# SCH_My-1st-flashing-led-pcb_2025-11-08.net
KiCad netlist of a schematic drawn in EasyEDA
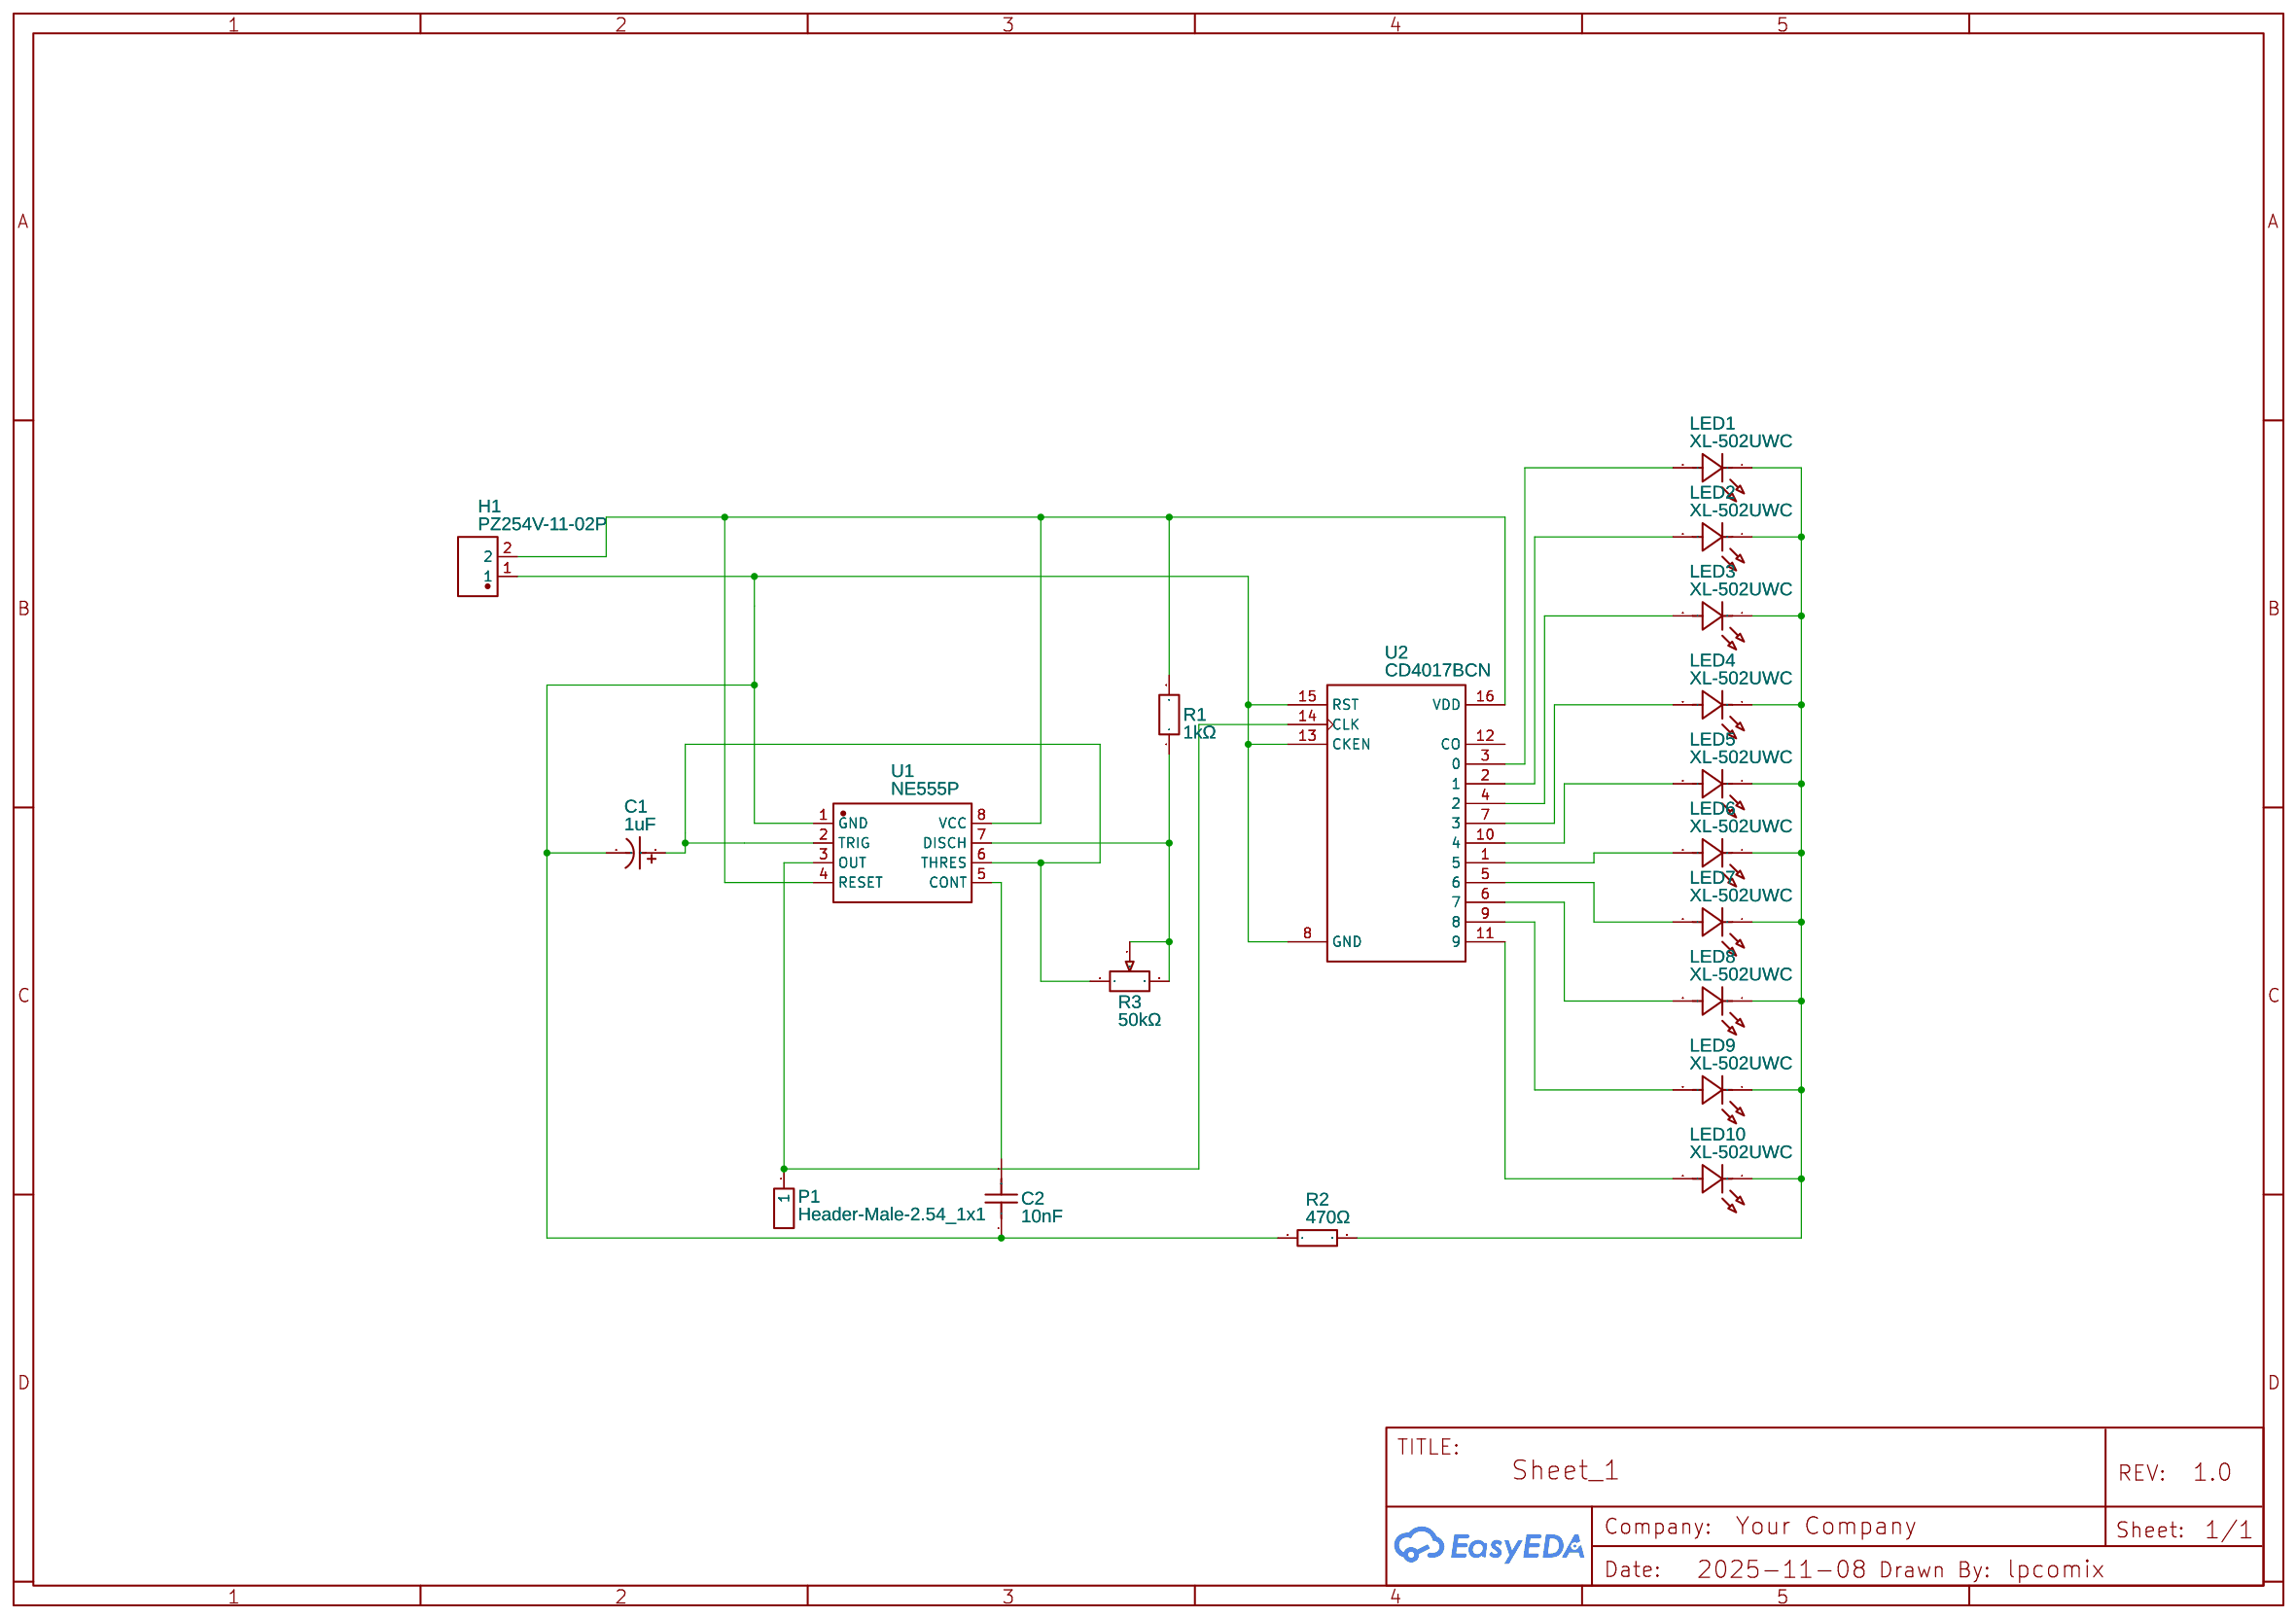
[diagram p0: schematic sheet]

(export (version "E")
  (design (tool "Eeschema 10.0.6"))
  (components
    (comp (ref "C1")
      (value "1uF")
      (fields (field (name "Manufacturer Part") "KF010M050C110A") (field (name "Manufacturer") "CapXon(丰宾)"))
      (libsource (lib "") (part "KF010M050C110A"))
    )
    (comp (ref "C2")
      (value "10nF")
      (fields (field (name "Manufacturer Part") "N09F1B103MN0B0S0N0") (field (name "Manufacturer") "STE(松田)"))
      (libsource (lib "") (part "N09F1B103MN0B0S0N0"))
    )
    (comp (ref "H1")
      (value "PZ254V-11-02P")
      (fields (field (name "Manufacturer") "XFCN(兴飞)"))
      (libsource (lib "") (part "PZ254V-11-02P"))
    )
    (comp (ref "LED1")
      (value "XL-502UWC")
      (fields (field (name "Manufacturer") "XINGLIGHT(成兴光)"))
      (libsource (lib "") (part "XL-502UWC"))
    )
    (comp (ref "LED2")
      (value "XL-502UWC")
      (fields (field (name "Manufacturer") "XINGLIGHT(成兴光)"))
      (libsource (lib "") (part "XL-502UWC"))
    )
    (comp (ref "LED3")
      (value "XL-502UWC")
      (fields (field (name "Manufacturer") "XINGLIGHT(成兴光)"))
      (libsource (lib "") (part "XL-502UWC"))
    )
    (comp (ref "LED4")
      (value "XL-502UWC")
      (fields (field (name "Manufacturer") "XINGLIGHT(成兴光)"))
      (libsource (lib "") (part "XL-502UWC"))
    )
    (comp (ref "LED5")
      (value "XL-502UWC")
      (fields (field (name "Manufacturer") "XINGLIGHT(成兴光)"))
      (libsource (lib "") (part "XL-502UWC"))
    )
    (comp (ref "LED6")
      (value "XL-502UWC")
      (fields (field (name "Manufacturer") "XINGLIGHT(成兴光)"))
      (libsource (lib "") (part "XL-502UWC"))
    )
    (comp (ref "LED7")
      (value "XL-502UWC")
      (fields (field (name "Manufacturer") "XINGLIGHT(成兴光)"))
      (libsource (lib "") (part "XL-502UWC"))
    )
    (comp (ref "LED8")
      (value "XL-502UWC")
      (fields (field (name "Manufacturer") "XINGLIGHT(成兴光)"))
      (libsource (lib "") (part "XL-502UWC"))
    )
    (comp (ref "LED9")
      (value "XL-502UWC")
      (fields (field (name "Manufacturer") "XINGLIGHT(成兴光)"))
      (libsource (lib "") (part "XL-502UWC"))
    )
    (comp (ref "LED10")
      (value "XL-502UWC")
      (fields (field (name "Manufacturer") "XINGLIGHT(成兴光)"))
      (libsource (lib "") (part "XL-502UWC"))
    )
    (comp (ref "P1")
      (value "Header-Male-2.54_1x1")
      (fields (field (name "Manufacturer Part") "2.54-1*1P针") (field (name "Manufacturer") "BOOMELE(博穆精密)"))
      (libsource (lib "") (part "Header-Male-2.54_1x1"))
    )
    (comp (ref "R1")
      (value "1kΩ")
      (fields (field (name "Manufacturer Part") "MF1/4W-1KΩ±1%T52") (field (name "Manufacturer") "华星机电"))
      (libsource (lib "") (part "MF1/4W-1KΩ±1%T52"))
    )
    (comp (ref "R2")
      (value "470Ω")
      (fields
        (field (name "Manufacturer Part") "MFR0W4F4700A50")
        (field (name "Manufacturer") "UNI-ROYAL(厚声)")
      )
      (libsource (lib "") (part "MFR0W4F4700A50"))
    )
    (comp (ref "R3")
      (value "50kΩ")
      (fields (field (name "Manufacturer Part") "3296X-1-503") (field (name "Manufacturer") "BOCHEN(博晨)"))
      (libsource (lib "") (part "3296X-1-503_C118912"))
    )
    (comp (ref "U1")
      (value "NE555P")
      (fields (field (name "Manufacturer") "TI(德州仪器)"))
      (libsource (lib "") (part "NE555P"))
    )
    (comp (ref "U2") (value "CD4017BCN") (libsource (lib "") (part "CD4017BCN")))
  )
  (nets
    (net (code "1") (name "Net-(LED1-A)") (class "Default")
      (node (ref "LED1") (pin "2") (pinfunction "A_2") (pintype "unspecified"))
      (node (ref "U2") (pin "3") (pinfunction "0_3") (pintype "output"))
    )
    (net (code "2") (name "Net-(LED1-K)") (class "Default")
      (node (ref "LED1") (pin "1") (pinfunction "K_1") (pintype "unspecified"))
      (node (ref "LED10") (pin "1") (pinfunction "K_1") (pintype "unspecified"))
      (node (ref "LED2") (pin "1") (pinfunction "K_1") (pintype "unspecified"))
      (node (ref "LED3") (pin "1") (pinfunction "K_1") (pintype "unspecified"))
      (node (ref "LED4") (pin "1") (pinfunction "K_1") (pintype "unspecified"))
      (node (ref "LED5") (pin "1") (pinfunction "K_1") (pintype "unspecified"))
      (node (ref "LED6") (pin "1") (pinfunction "K_1") (pintype "unspecified"))
      (node (ref "LED7") (pin "1") (pinfunction "K_1") (pintype "unspecified"))
      (node (ref "LED8") (pin "1") (pinfunction "K_1") (pintype "unspecified"))
      (node (ref "LED9") (pin "1") (pinfunction "K_1") (pintype "unspecified"))
      (node (ref "R2") (pin "2") (pinfunction "2_2") (pintype "input"))
    )
    (net (code "3") (name "Net-(LED2-A)") (class "Default")
      (node (ref "LED2") (pin "2") (pinfunction "A_2") (pintype "unspecified"))
      (node (ref "U2") (pin "2") (pinfunction "1_2") (pintype "output"))
    )
    (net (code "4") (name "Net-(LED3-A)") (class "Default")
      (node (ref "LED3") (pin "2") (pinfunction "A_2") (pintype "unspecified"))
      (node (ref "U2") (pin "4") (pinfunction "2_4") (pintype "output"))
    )
    (net (code "5") (name "Net-(LED4-A)") (class "Default")
      (node (ref "LED4") (pin "2") (pinfunction "A_2") (pintype "unspecified"))
      (node (ref "U2") (pin "7") (pinfunction "3_7") (pintype "output"))
    )
    (net (code "6") (name "Net-(LED5-A)") (class "Default")
      (node (ref "LED5") (pin "2") (pinfunction "A_2") (pintype "unspecified"))
      (node (ref "U2") (pin "10") (pinfunction "4_10") (pintype "output"))
    )
    (net (code "7") (name "Net-(LED6-A)") (class "Default")
      (node (ref "LED6") (pin "2") (pinfunction "A_2") (pintype "unspecified"))
      (node (ref "U2") (pin "1") (pinfunction "5_1") (pintype "output"))
    )
    (net (code "8") (name "Net-(LED7-A)") (class "Default")
      (node (ref "LED7") (pin "2") (pinfunction "A_2") (pintype "unspecified"))
      (node (ref "U2") (pin "5") (pinfunction "6_5") (pintype "output"))
    )
    (net (code "9") (name "Net-(LED8-A)") (class "Default")
      (node (ref "LED8") (pin "2") (pinfunction "A_2") (pintype "unspecified"))
      (node (ref "U2") (pin "6") (pinfunction "7_6") (pintype "output"))
    )
    (net (code "10") (name "Net-(LED9-A)") (class "Default")
      (node (ref "LED9") (pin "2") (pinfunction "A_2") (pintype "unspecified"))
      (node (ref "U2") (pin "9") (pinfunction "8_9") (pintype "output"))
    )
    (net (code "11") (name "Net-(LED10-A)") (class "Default")
      (node (ref "LED10") (pin "2") (pinfunction "A_2") (pintype "unspecified"))
      (node (ref "U2") (pin "11") (pinfunction "9_11") (pintype "output"))
    )
    (net (code "12") (name "Net-(U1-CONT)") (class "Default")
      (node (ref "C2") (pin "2") (pinfunction "2_2") (pintype "unspecified"))
      (node (ref "U1") (pin "5") (pinfunction "CONT_5") (pintype "unspecified"))
    )
    (net (code "13") (name "Net-(U1-DISCH)") (class "Default")
      (node (ref "R1") (pin "1") (pinfunction "1_1") (pintype "unspecified"))
      (node (ref "R3") (pin "2") (pinfunction "2_2") (pintype "input"))
      (node (ref "R3") (pin "3") (pinfunction "3_3") (pintype "input"))
      (node (ref "U1") (pin "7") (pinfunction "DISCH_7") (pintype "unspecified"))
    )
    (net (code "14") (name "Net-(U1-GND)") (class "Default")
      (node (ref "C1") (pin "2") (pinfunction "2_2") (pintype "input"))
      (node (ref "C2") (pin "1") (pinfunction "1_1") (pintype "unspecified"))
      (node (ref "H1") (pin "1") (pinfunction "1_1") (pintype "unspecified"))
      (node (ref "R2") (pin "1") (pinfunction "1_1") (pintype "input"))
      (node (ref "U1") (pin "1") (pinfunction "GND_1") (pintype "unspecified"))
      (node (ref "U2") (pin "13") (pinfunction "CKEN_13") (pintype "unspecified"))
      (node (ref "U2") (pin "15") (pinfunction "RST_15") (pintype "unspecified"))
      (node (ref "U2") (pin "8") (pinfunction "GND_8") (pintype "passive"))
    )
    (net (code "15") (name "Net-(U1-OUT)") (class "Default")
      (node (ref "P1") (pin "1") (pinfunction "1_1") (pintype "input"))
      (node (ref "U1") (pin "3") (pinfunction "OUT_3") (pintype "unspecified"))
      (node (ref "U2") (pin "14") (pinfunction "CLK_14") (pintype "unspecified"))
    )
    (net (code "16") (name "Net-(U1-RESET)") (class "Default")
      (node (ref "H1") (pin "2") (pinfunction "2_2") (pintype "unspecified"))
      (node (ref "R1") (pin "2") (pinfunction "2_2") (pintype "unspecified"))
      (node (ref "U1") (pin "4") (pinfunction "RESET_4") (pintype "unspecified"))
      (node (ref "U1") (pin "8") (pinfunction "VCC_8") (pintype "unspecified"))
      (node (ref "U2") (pin "16") (pinfunction "VDD_16") (pintype "passive"))
    )
    (net (code "17") (name "Net-(U1-THRES)") (class "Default")
      (node (ref "C1") (pin "1") (pinfunction "1_1") (pintype "input"))
      (node (ref "R3") (pin "1") (pinfunction "1_1") (pintype "input"))
      (node (ref "U1") (pin "2") (pinfunction "TRIG_2") (pintype "unspecified"))
      (node (ref "U1") (pin "6") (pinfunction "THRES_6") (pintype "unspecified"))
    )
    (net (code "18") (name "unconnected-(U2-CO-Pad12)") (class "Default")
      (node (ref "U2") (pin "12") (pinfunction "CO_12") (pintype "output"))
    )
  )
)
